# SD_Card_Module.net
KiCad netlist of a schematic drawn in Altium Designer
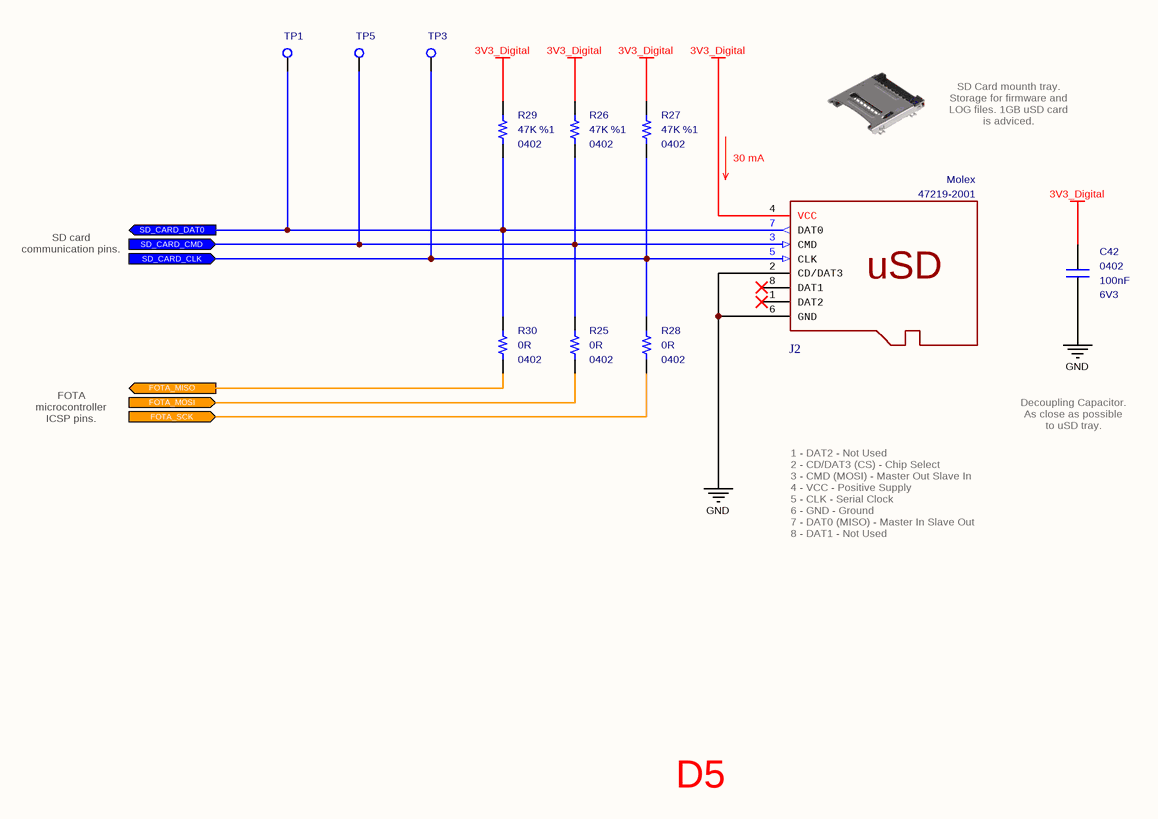
[diagram p0: SD Card Module.SchDoc]

(export (version "E")
  (design (tool "Eeschema 10.0.6"))
  (components
    (comp (ref "C42")
      (value "100nF")
      (footprint "CAPACITOR_0402")
      (description "Capacitor - 100nF [0402-6V3] (Ceramic)")
      (fields
        (field (name "MANUFACTURER_PART_NUMBER") "04026D104KAT4A")
        (field (name "MOUSER_PART_NUMBER") "581-04026D104KAT4A")
        (field (name "CASE") "0402")
        (field (name "VOLTAGE") "6V3")
      )
      (libsource (lib "Ovoo_Schematic") (part "Capacitor - 100nF [0402-6V3]"))
    )
    (comp (ref "J2")
      (value "Memory Card Connectors")
      (footprint "Connector - SD Module")
      (description "Memory Card Connectors TFR READER (HINGE TYPE)")
      (fields
        (field (name "MOUSER_PART_NUMBER") "538-47219-2001")
        (field (name "MANUFACTURER_PART_NUMBER") "47219-2001")
        (field (name "MANUFACTURER_NAME") "Molex")
      )
      (libsource (lib "Ovoo_Schematic") (part "Connector - SD Slot"))
    )
    (comp (ref "R25")
      (value "0R")
      (footprint "RESISTOR_0402")
      (description "Thick Film Resistors - SMD 1/16 W 0 Ohms")
      (fields
        (field (name "MANUFACTURER_PART_NUMBER") "CRCW04020000Z0ED")
        (field (name "MOUSER_PART_NUMBER") "71-CRCW0402-0-E3")
        (field (name "CASE") "0402")
      )
      (libsource (lib "Ovoo_Schematic") (part "Resistor - 0R"))
    )
    (comp (ref "R26")
      (value "47K")
      (footprint "RESISTOR_0402")
      (description "Thick Film Resistors - SMD 1/16 W 47 Kohms 1%")
      (fields
        (field (name "MANUFACTURER_PART_NUMBER") "CRCW040247K0FKED")
        (field (name "MOUSER_PART_NUMBER") "71-CRCW0402-47K-E3")
        (field (name "TOLERANCE") "%1")
        (field (name "CASE") "0402")
      )
      (libsource (lib "Ovoo_Schematic") (part "Resistor - 47K"))
    )
    (comp (ref "R27")
      (value "47K")
      (footprint "RESISTOR_0402")
      (description "Thick Film Resistors - SMD 1/16 W 47 Kohms 1%")
      (fields
        (field (name "MANUFACTURER_PART_NUMBER") "CRCW040247K0FKED")
        (field (name "MOUSER_PART_NUMBER") "71-CRCW0402-47K-E3")
        (field (name "TOLERANCE") "%1")
        (field (name "CASE") "0402")
      )
      (libsource (lib "Ovoo_Schematic") (part "Resistor - 47K"))
    )
    (comp (ref "R28")
      (value "0R")
      (footprint "RESISTOR_0402")
      (description "Thick Film Resistors - SMD 1/16 W 0 Ohms")
      (fields
        (field (name "MANUFACTURER_PART_NUMBER") "CRCW04020000Z0ED")
        (field (name "MOUSER_PART_NUMBER") "71-CRCW0402-0-E3")
        (field (name "CASE") "0402")
      )
      (libsource (lib "Ovoo_Schematic") (part "Resistor - 0R"))
    )
    (comp (ref "R29")
      (value "47K")
      (footprint "RESISTOR_0402")
      (description "Thick Film Resistors - SMD 1/16 W 47 Kohms 1%")
      (fields
        (field (name "MANUFACTURER_PART_NUMBER") "CRCW040247K0FKED")
        (field (name "MOUSER_PART_NUMBER") "71-CRCW0402-47K-E3")
        (field (name "TOLERANCE") "%1")
        (field (name "CASE") "0402")
      )
      (libsource (lib "Ovoo_Schematic") (part "Resistor - 47K"))
    )
    (comp (ref "R30")
      (value "0R")
      (footprint "RESISTOR_0402")
      (description "Thick Film Resistors - SMD 1/16 W 0 Ohms")
      (fields
        (field (name "MANUFACTURER_PART_NUMBER") "CRCW04020000Z0ED")
        (field (name "MOUSER_PART_NUMBER") "71-CRCW0402-0-E3")
        (field (name "CASE") "0402")
      )
      (libsource (lib "Ovoo_Schematic") (part "Resistor - 0R"))
    )
    (comp (ref "TP1")
      (value "PCB - Test Point")
      (footprint "Test_Pad - Hole")
      (description "Test Point")
      (libsource (lib "Ovoo_Schematic") (part "PCB - Test Point"))
    )
    (comp (ref "TP3")
      (value "PCB - Test Point")
      (footprint "Test_Pad - Hole")
      (description "Test Point")
      (libsource (lib "Ovoo_Schematic") (part "PCB - Test Point"))
    )
    (comp (ref "TP5")
      (value "PCB - Test Point")
      (footprint "Test_Pad - Hole")
      (description "Test Point")
      (libsource (lib "Ovoo_Schematic") (part "PCB - Test Point"))
    )
  )
  (nets
    (net (code "1") (name "/FOTA_MISO") (class "Default")
      (node (ref "R30") (pin "1") (pinfunction "1_1") (pintype "passive"))
    )
    (net (code "2") (name "/FOTA_MOSI") (class "Default")
      (node (ref "R25") (pin "1") (pinfunction "1_1") (pintype "passive"))
    )
    (net (code "3") (name "/FOTA_SCK") (class "Default")
      (node (ref "R28") (pin "1") (pinfunction "1_1") (pintype "passive"))
    )
    (net (code "4") (name "/SD_CARD_CLK") (class "Default")
      (node (ref "J2") (pin "5") (pinfunction "CLK_5") (pintype "input"))
      (node (ref "R27") (pin "1") (pinfunction "1_1") (pintype "passive"))
      (node (ref "R28") (pin "2") (pinfunction "2_2") (pintype "passive"))
      (node (ref "TP3") (pin "1") (pinfunction "1_1") (pintype "passive"))
    )
    (net (code "5") (name "/SD_CARD_CMD") (class "Default")
      (node (ref "J2") (pin "3") (pinfunction "CMD_3") (pintype "input"))
      (node (ref "R25") (pin "2") (pinfunction "2_2") (pintype "passive"))
      (node (ref "R26") (pin "1") (pinfunction "1_1") (pintype "passive"))
      (node (ref "TP5") (pin "1") (pinfunction "1_1") (pintype "passive"))
    )
    (net (code "6") (name "/SD_CARD_DAT0") (class "Default")
      (node (ref "J2") (pin "7") (pinfunction "DAT0_7") (pintype "output"))
      (node (ref "R29") (pin "1") (pinfunction "1_1") (pintype "passive"))
      (node (ref "R30") (pin "2") (pinfunction "2_2") (pintype "passive"))
      (node (ref "TP1") (pin "1") (pinfunction "1_1") (pintype "passive"))
    )
    (net (code "7") (name "3V3_Digital") (class "Default")
      (node (ref "C42") (pin "2") (pinfunction "2_2") (pintype "passive"))
      (node (ref "J2") (pin "4") (pinfunction "VCC_4") (pintype "passive"))
      (node (ref "R26") (pin "2") (pinfunction "2_2") (pintype "passive"))
      (node (ref "R27") (pin "2") (pinfunction "2_2") (pintype "passive"))
      (node (ref "R29") (pin "2") (pinfunction "2_2") (pintype "passive"))
    )
    (net (code "8") (name "GND") (class "Default")
      (node (ref "C42") (pin "1") (pinfunction "1_1") (pintype "passive"))
      (node (ref "J2") (pin "2") (pinfunction "CD/DAT3_2") (pintype "passive"))
      (node (ref "J2") (pin "6") (pinfunction "GND_6") (pintype "passive"))
    )
    (net (code "9") (name "unconnected-(J2-DAT1-Pad8)") (class "Default")
      (node (ref "J2") (pin "8") (pinfunction "DAT1_8") (pintype "passive+no_connect"))
    )
    (net (code "10") (name "unconnected-(J2-DAT2-Pad1)") (class "Default")
      (node (ref "J2") (pin "1") (pinfunction "DAT2_1") (pintype "passive+no_connect"))
    )
  )
)
